# Overview.net
KiCad netlist of a schematic drawn in Altium Designer
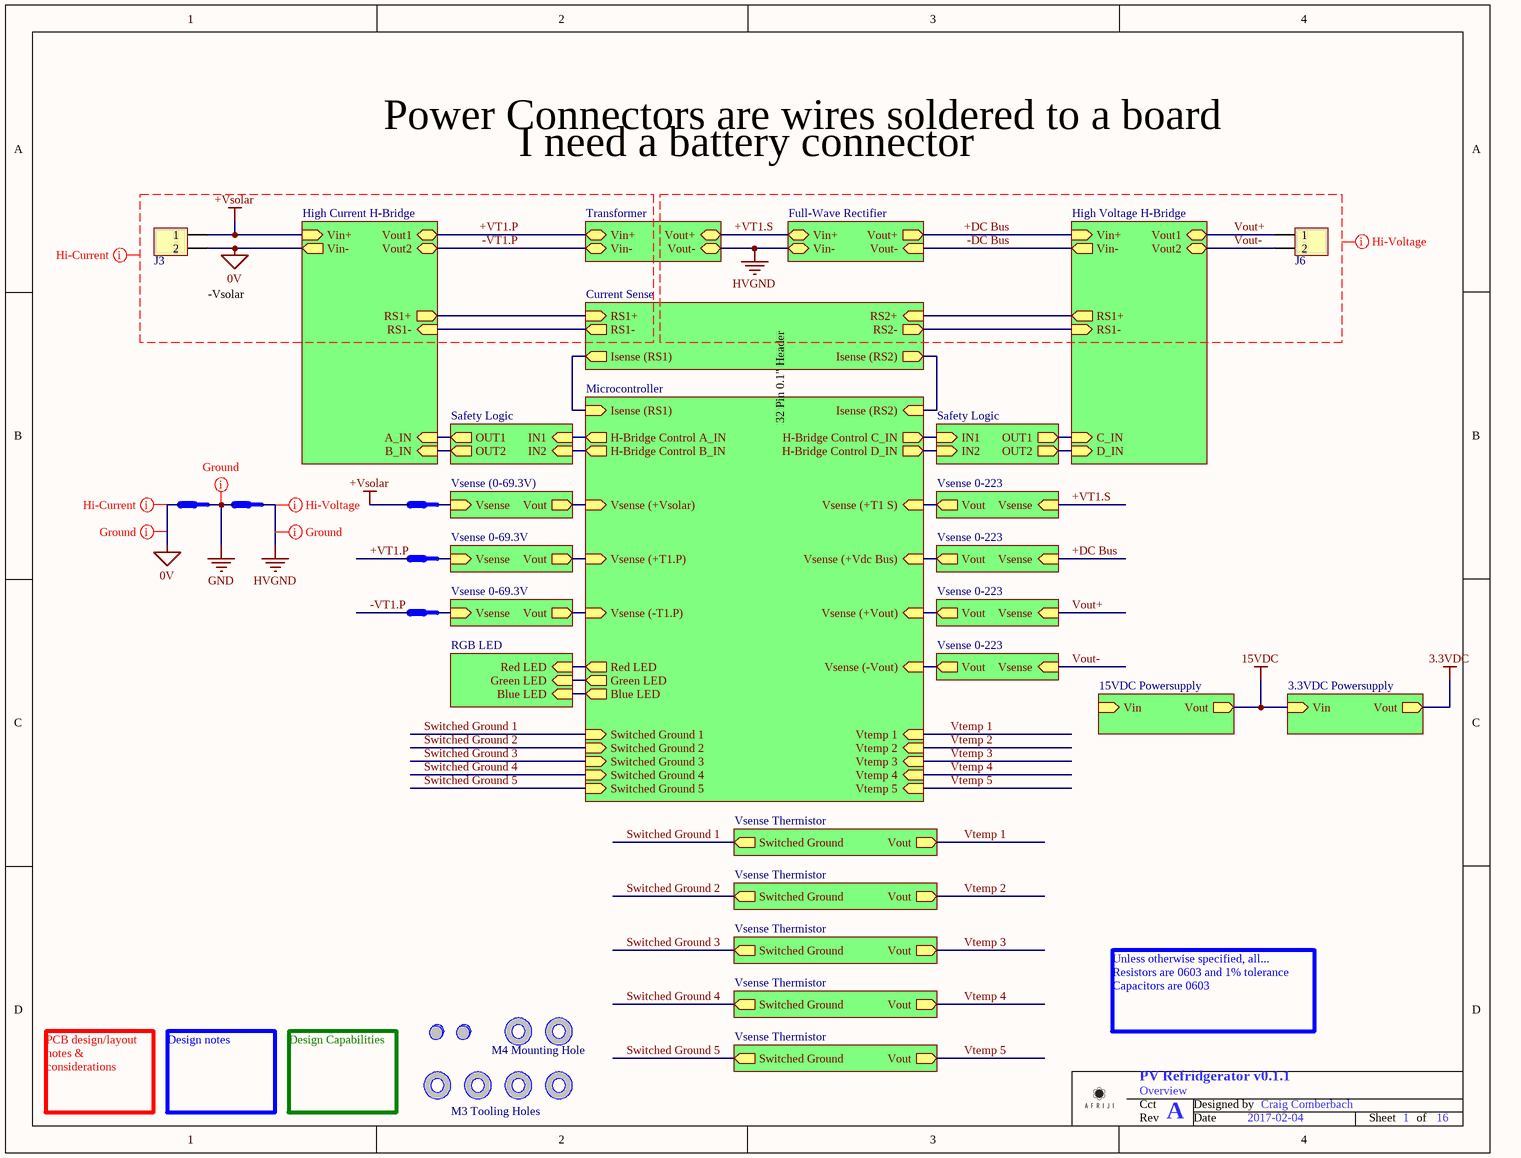
[diagram p0: Overview.SchDoc]

(export (version "E")
  (design (tool "Eeschema 10.0.6"))
  (components
    (comp (ref "FD1")
      (value "Fiducial, Double Sided")
      (footprint "Fiducial - Double sided")
      (libsource (lib "Integrated Component Library") (part "Fiducial, Double Sided"))
    )
    (comp (ref "FD2")
      (value "Fiducial, Double Sided")
      (footprint "Fiducial - Double sided")
      (libsource (lib "Integrated Component Library") (part "Fiducial, Double Sided"))
    )
    (comp (ref "J3")
      (value "Terminal Block - 2-Position HiV/HiA")
      (footprint "TE 796739-2")
      (fields
        (field (name "MANUFACTURER") "TE Connectivity AMP Connectors")
        (field (name "MANUFACTURER PART NUMBER") "796739-2")
        (field (name "VOLTAGE") "600V")
      )
      (libsource (lib "Local Library") (part "Terminal Block - 2-Position HiV/HiA"))
    )
    (comp (ref "J6")
      (value "Terminal Block - 2-Position HiV/HiA")
      (footprint "TE 796739-2")
      (fields
        (field (name "MANUFACTURER") "TE Connectivity AMP Connectors")
        (field (name "MANUFACTURER PART NUMBER") "796739-2")
        (field (name "VOLTAGE") "600V")
      )
      (libsource (lib "") (part "Terminal Block - 2-Position HiV/HiA_1"))
    )
    (comp (ref "MountingHole1")
      (value "M3 Tooling Holes")
      (footprint "M3 Screw - One Sided")
      (libsource (lib "Personal Library") (part "Mounting Hole"))
    )
    (comp (ref "MountingHole2")
      (value "Mounting Hole")
      (footprint "M3 Screw - One Sided")
      (libsource (lib "Personal Library") (part "Mounting Hole"))
    )
    (comp (ref "MountingHole3")
      (value "Mounting Hole")
      (footprint "M4 Screw - One Sided")
      (libsource (lib "Personal Library") (part "Mounting Hole"))
    )
    (comp (ref "MountingHole4")
      (value "M4 Mounting Hole")
      (footprint "M4 Screw - One Sided")
      (libsource (lib "Personal Library") (part "Mounting Hole"))
    )
    (comp (ref "MountingHole5")
      (value "Mounting Hole")
      (footprint "M3 Screw - One Sided")
      (libsource (lib "Personal Library") (part "Mounting Hole"))
    )
    (comp (ref "MountingHole6")
      (value "Mounting Hole")
      (footprint "M3 Screw - One Sided")
      (libsource (lib "Personal Library") (part "Mounting Hole"))
    )
    (comp (ref "NetTie2")
      (value "Net Tie")
      (footprint "Net tie (7/50 mil)")
      (description "Ties two nets together")
      (libsource (lib "Integrated Component Library") (part "Net Tie"))
    )
    (comp (ref "NetTie3")
      (value "Net Tie")
      (footprint "Net tie (7/7 mil)")
      (description "Ties two nets together")
      (libsource (lib "Integrated Component Library") (part "Net Tie"))
    )
    (comp (ref "NetTie7")
      (value "Net Tie")
      (footprint "Net tie (7/7 mil)")
      (description "Ties two nets together")
      (libsource (lib "Integrated Component Library") (part "Net Tie"))
    )
    (comp (ref "NetTie8")
      (value "Net Tie")
      (footprint "Net tie (7/7 mil)")
      (description "Ties two nets together")
      (libsource (lib "Integrated Component Library") (part "Net Tie"))
    )
    (comp (ref "NetTie9")
      (value "Net Tie")
      (footprint "Net tie (7/7 mil)")
      (description "Ties two nets together")
      (libsource (lib "Integrated Component Library") (part "Net Tie"))
    )
  )
  (nets
    (net (code "1") (name "+Vsolar") (class "Default")
      (node (ref "J3") (pin "1") (pinfunction "1_1") (pintype "passive"))
      (node (ref "NetTie7") (pin "2") (pinfunction "2_2") (pintype "passive"))
    )
    (net (code "3") (name "/+VT1.P") (class "Default")
      (node (ref "NetTie8") (pin "2") (pinfunction "2_2") (pintype "passive"))
    )
    (net (code "6") (name "/-VT1.P") (class "Default")
      (node (ref "NetTie9") (pin "2") (pinfunction "2_2") (pintype "passive"))
    )
    (net (code "31") (name "/Vout+") (class "Default")
      (node (ref "J6") (pin "1") (pinfunction "1_1") (pintype "passive"))
    )
    (net (code "32") (name "/Vout-") (class "Default")
      (node (ref "J6") (pin "2") (pinfunction "2_2") (pintype "passive"))
    )
    (net (code "39") (name "/Vsense") (class "Default")
      (node (ref "NetTie9") (pin "1") (pinfunction "1_1") (pintype "passive"))
    )
    (net (code "40") (name "/Vsense_1") (class "Default")
      (node (ref "NetTie7") (pin "1") (pinfunction "1_1") (pintype "passive"))
    )
    (net (code "41") (name "/Vsense_2") (class "Default")
      (node (ref "NetTie8") (pin "1") (pinfunction "1_1") (pintype "passive"))
    )
    (net (code "47") (name "0V") (class "Default")
      (node (ref "J3") (pin "2") (pinfunction "2_2") (pintype "passive"))
      (node (ref "NetTie2") (pin "2") (pinfunction "2_2") (pintype "passive"))
    )
    (net (code "50") (name "GND") (class "Default")
      (node (ref "NetTie2") (pin "1") (pinfunction "1_1") (pintype "passive"))
      (node (ref "NetTie3") (pin "2") (pinfunction "2_2") (pintype "passive"))
    )
    (net (code "51") (name "HVGND") (class "Default")
      (node (ref "NetTie3") (pin "1") (pinfunction "1_1") (pintype "passive"))
    )
  )
)
